# STM32.net
KiCad netlist of a schematic drawn in Altium Designer
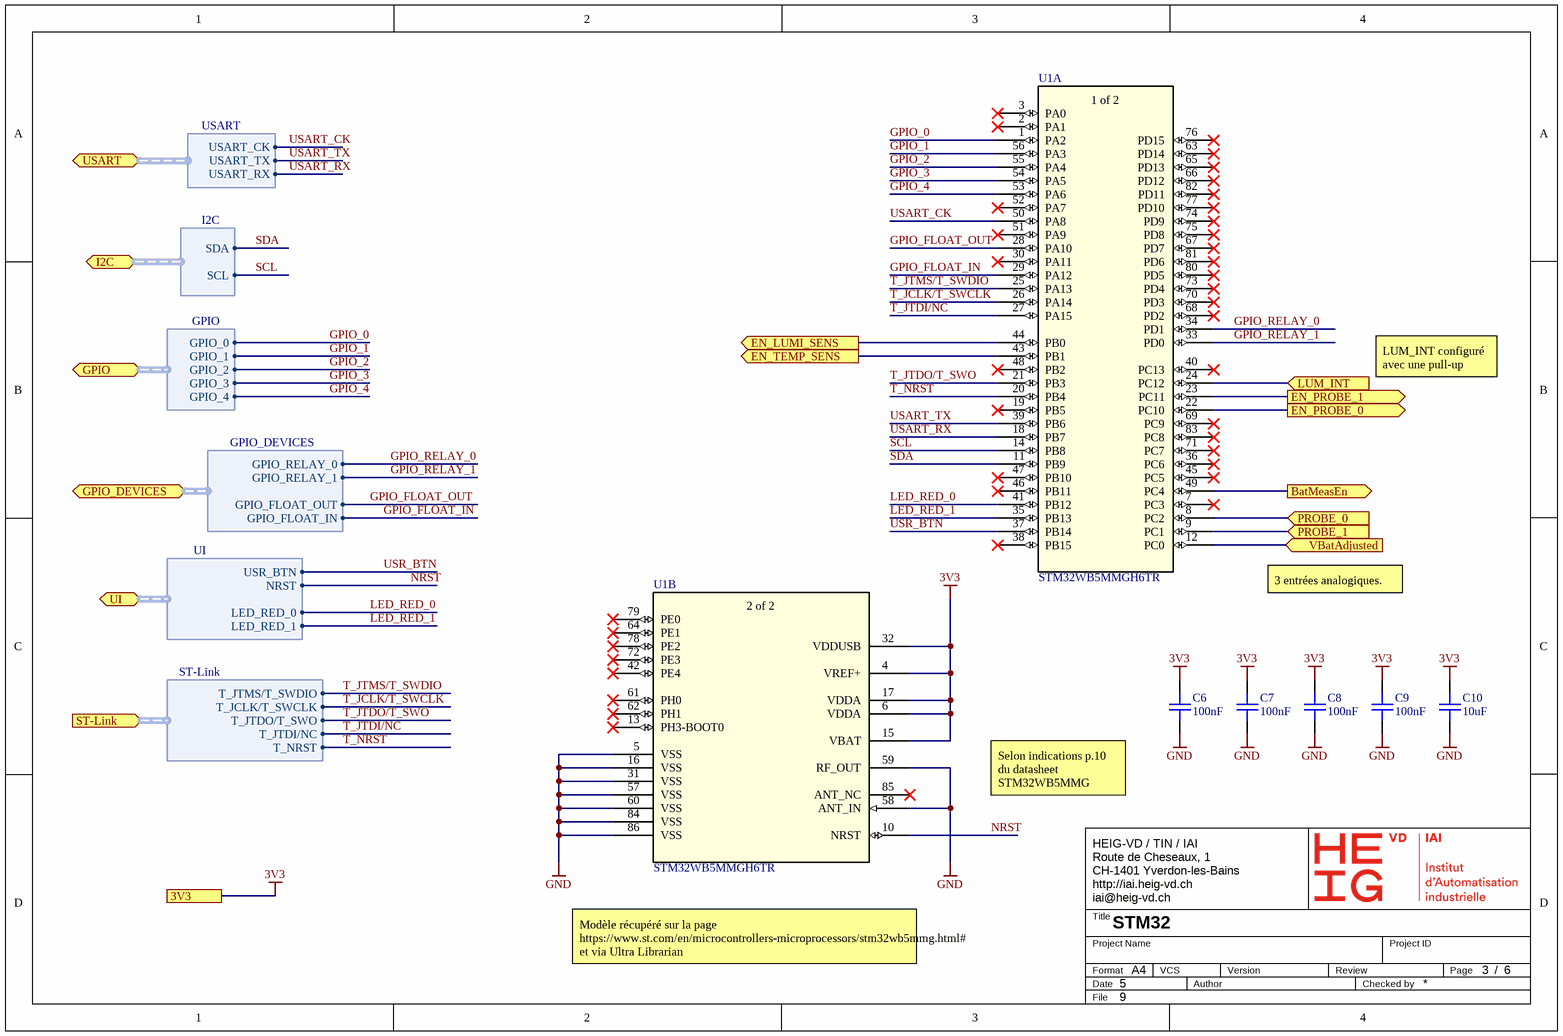
[diagram p0: STM32.SchDoc]

(export (version "E")
  (design (tool "Eeschema 10.0.6"))
  (components
    (comp (ref "C6")
      (value "100nF")
      (footprint "CAPC1005X05N")
      (description "100nF 10% 50V Ceramic Capacitor X8L 0402 (1005 Metric)")
      (fields (field (name "TOLERANCE") "10%"))
      (libsource (lib "HEIG-VD Pro") (part "Capacitor"))
    )
    (comp (ref "C7")
      (value "100nF")
      (footprint "CAPC1005X05N")
      (description "100nF 10% 50V Ceramic Capacitor X8L 0402 (1005 Metric)")
      (fields (field (name "TOLERANCE") "10%"))
      (libsource (lib "HEIG-VD Pro") (part "Capacitor"))
    )
    (comp (ref "C8")
      (value "100nF")
      (footprint "CAPC1005X05N")
      (description "100nF 10% 50V Ceramic Capacitor X8L 0402 (1005 Metric)")
      (fields (field (name "TOLERANCE") "10%"))
      (libsource (lib "HEIG-VD Pro") (part "Capacitor"))
    )
    (comp (ref "C9")
      (value "100nF")
      (footprint "CAPC1005X05N")
      (description "100nF 10% 50V Ceramic Capacitor X8L 0402 (1005 Metric)")
      (fields (field (name "TOLERANCE") "10%"))
      (libsource (lib "HEIG-VD Pro") (part "Capacitor"))
    )
    (comp (ref "C10")
      (value "10uF")
      (footprint "CAPC3216X18N")
      (description "10 µF ±10% 50V Ceramic Capacitor X7R 1206 (3216 Metric)")
      (fields (field (name "TOLERANCE") "10%"))
      (libsource (lib "HEIG-VD Pro") (part "Capacitor"))
    )
    (comp (ref "U1")
      (value "STM32WB5MMGH6TR")
      (footprint "SIP-LGA86_STM")
      (description "No Description Available")
      (libsource (lib "STM32WB5MMGH6TR") (part "STM32WB5MMGH6TR"))
    )
  )
  (nets
    (net (code "7") (name "/BatMeasEn") (class "Default")
      (node (ref "U1") (pin "49") (pinfunction "PC4_49") (pintype "bidirectional"))
    )
    (net (code "8") (name "/EN_LUMI_SENS") (class "Default")
      (node (ref "U1") (pin "44") (pinfunction "PB0_44") (pintype "bidirectional"))
    )
    (net (code "9") (name "/EN_PROBE_0") (class "Default")
      (node (ref "U1") (pin "22") (pinfunction "PC10_22") (pintype "bidirectional"))
    )
    (net (code "10") (name "/EN_PROBE_1") (class "Default")
      (node (ref "U1") (pin "23") (pinfunction "PC11_23") (pintype "bidirectional"))
    )
    (net (code "11") (name "/EN_TEMP_SENS") (class "Default")
      (node (ref "U1") (pin "43") (pinfunction "PB1_43") (pintype "bidirectional"))
    )
    (net (code "12") (name "/GPIO_0") (class "Default")
      (node (ref "U1") (pin "1") (pinfunction "PA2_1") (pintype "bidirectional"))
    )
    (net (code "13") (name "/GPIO_1") (class "Default")
      (node (ref "U1") (pin "56") (pinfunction "PA3_56") (pintype "bidirectional"))
    )
    (net (code "14") (name "/GPIO_2") (class "Default")
      (node (ref "U1") (pin "55") (pinfunction "PA4_55") (pintype "bidirectional"))
    )
    (net (code "15") (name "/GPIO_3") (class "Default")
      (node (ref "U1") (pin "54") (pinfunction "PA5_54") (pintype "bidirectional"))
    )
    (net (code "16") (name "/GPIO_4") (class "Default")
      (node (ref "U1") (pin "53") (pinfunction "PA6_53") (pintype "bidirectional"))
    )
    (net (code "17") (name "/GPIO_FLOAT_IN") (class "Default")
      (node (ref "U1") (pin "29") (pinfunction "PA12_29") (pintype "bidirectional"))
    )
    (net (code "18") (name "/GPIO_FLOAT_OUT") (class "Default")
      (node (ref "U1") (pin "28") (pinfunction "PA10_28") (pintype "bidirectional"))
    )
    (net (code "19") (name "/GPIO_RELAY_0") (class "Default")
      (node (ref "U1") (pin "34") (pinfunction "PD1_34") (pintype "bidirectional"))
    )
    (net (code "20") (name "/GPIO_RELAY_1") (class "Default")
      (node (ref "U1") (pin "33") (pinfunction "PD0_33") (pintype "bidirectional"))
    )
    (net (code "21") (name "/LED_RED_0") (class "Default")
      (node (ref "U1") (pin "41") (pinfunction "PB12_41") (pintype "bidirectional"))
    )
    (net (code "22") (name "/LED_RED_1") (class "Default")
      (node (ref "U1") (pin "35") (pinfunction "PB13_35") (pintype "bidirectional"))
    )
    (net (code "23") (name "/LUM_INT") (class "Default")
      (node (ref "U1") (pin "24") (pinfunction "PC12_24") (pintype "bidirectional"))
    )
    (net (code "24") (name "/NRST") (class "Default")
      (node (ref "U1") (pin "10") (pinfunction "NRST_10") (pintype "bidirectional"))
    )
    (net (code "25") (name "/PROBE_0") (class "Default")
      (node (ref "U1") (pin "8") (pinfunction "PC2_8") (pintype "bidirectional"))
    )
    (net (code "26") (name "/PROBE_1") (class "Default")
      (node (ref "U1") (pin "9") (pinfunction "PC1_9") (pintype "bidirectional"))
    )
    (net (code "27") (name "/SCL") (class "Default")
      (node (ref "U1") (pin "14") (pinfunction "PB8_14") (pintype "bidirectional"))
    )
    (net (code "28") (name "/SDA") (class "Default")
      (node (ref "U1") (pin "11") (pinfunction "PB9_11") (pintype "bidirectional"))
    )
    (net (code "29") (name "/T_JCLK{slash}T_SWCLK") (class "Default")
      (node (ref "U1") (pin "26") (pinfunction "PA14_26") (pintype "bidirectional"))
    )
    (net (code "30") (name "/T_JTDI{slash}NC") (class "Default")
      (node (ref "U1") (pin "27") (pinfunction "PA15_27") (pintype "bidirectional"))
    )
    (net (code "31") (name "/T_JTDO{slash}T_SWO") (class "Default")
      (node (ref "U1") (pin "21") (pinfunction "PB3_21") (pintype "bidirectional"))
    )
    (net (code "32") (name "/T_JTMS{slash}T_SWDIO") (class "Default")
      (node (ref "U1") (pin "25") (pinfunction "PA13_25") (pintype "bidirectional"))
    )
    (net (code "33") (name "/T_NRST") (class "Default")
      (node (ref "U1") (pin "20") (pinfunction "PB4_20") (pintype "bidirectional"))
    )
    (net (code "34") (name "/USART_CK") (class "Default")
      (node (ref "U1") (pin "50") (pinfunction "PA8_50") (pintype "bidirectional"))
    )
    (net (code "35") (name "/USART_RX") (class "Default")
      (node (ref "U1") (pin "18") (pinfunction "PB7_18") (pintype "bidirectional"))
    )
    (net (code "36") (name "/USART_TX") (class "Default")
      (node (ref "U1") (pin "39") (pinfunction "PB6_39") (pintype "bidirectional"))
    )
    (net (code "37") (name "/USR_BTN") (class "Default")
      (node (ref "U1") (pin "37") (pinfunction "PB14_37") (pintype "bidirectional"))
    )
    (net (code "38") (name "/VBatAdjusted") (class "Default")
      (node (ref "U1") (pin "12") (pinfunction "PC0_12") (pintype "bidirectional"))
    )
    (net (code "45") (name "3V3") (class "Default")
      (node (ref "C10") (pin "2") (pinfunction "2_2") (pintype "passive"))
      (node (ref "C6") (pin "1") (pinfunction "1_1") (pintype "passive"))
      (node (ref "C7") (pin "1") (pinfunction "1_1") (pintype "passive"))
      (node (ref "C8") (pin "1") (pinfunction "1_1") (pintype "passive"))
      (node (ref "C9") (pin "1") (pinfunction "1_1") (pintype "passive"))
      (node (ref "U1") (pin "15") (pinfunction "VBAT_15") (pintype "power_in"))
      (node (ref "U1") (pin "17") (pinfunction "VDDA_17") (pintype "power_in"))
      (node (ref "U1") (pin "32") (pinfunction "VDDUSB_32") (pintype "power_in"))
      (node (ref "U1") (pin "4") (pinfunction "VREF+_4") (pintype "power_in"))
      (node (ref "U1") (pin "6") (pinfunction "VDDA_6") (pintype "power_in"))
    )
    (net (code "46") (name "GND") (class "Default")
      (node (ref "C10") (pin "1") (pinfunction "1_1") (pintype "passive"))
      (node (ref "C6") (pin "2") (pinfunction "2_2") (pintype "passive"))
      (node (ref "C7") (pin "2") (pinfunction "2_2") (pintype "passive"))
      (node (ref "C8") (pin "2") (pinfunction "2_2") (pintype "passive"))
      (node (ref "C9") (pin "2") (pinfunction "2_2") (pintype "passive"))
      (node (ref "U1") (pin "16") (pinfunction "VSS_16") (pintype "power_in"))
      (node (ref "U1") (pin "31") (pinfunction "VSS_31") (pintype "power_in"))
      (node (ref "U1") (pin "5") (pinfunction "VSS_5") (pintype "power_in"))
      (node (ref "U1") (pin "57") (pinfunction "VSS_57") (pintype "power_in"))
      (node (ref "U1") (pin "58") (pinfunction "ANT_IN_58") (pintype "input"))
      (node (ref "U1") (pin "59") (pinfunction "RF_OUT_59") (pintype "output"))
      (node (ref "U1") (pin "60") (pinfunction "VSS_60") (pintype "power_in"))
      (node (ref "U1") (pin "84") (pinfunction "VSS_84") (pintype "power_in"))
      (node (ref "U1") (pin "86") (pinfunction "VSS_86") (pintype "power_in"))
    )
    (net (code "47") (name "unconnected-(U1A-PA0-Pad3)") (class "Default")
      (node (ref "U1") (pin "3") (pinfunction "PA0_3") (pintype "bidirectional+no_connect"))
    )
    (net (code "48") (name "unconnected-(U1A-PA1-Pad2)") (class "Default")
      (node (ref "U1") (pin "2") (pinfunction "PA1_2") (pintype "bidirectional+no_connect"))
    )
    (net (code "49") (name "unconnected-(U1A-PA7-Pad52)") (class "Default")
      (node (ref "U1") (pin "52") (pinfunction "PA7_52") (pintype "bidirectional+no_connect"))
    )
    (net (code "50") (name "unconnected-(U1A-PA9-Pad51)") (class "Default")
      (node (ref "U1") (pin "51") (pinfunction "PA9_51") (pintype "bidirectional+no_connect"))
    )
    (net (code "51") (name "unconnected-(U1A-PA11-Pad30)") (class "Default")
      (node (ref "U1") (pin "30") (pinfunction "PA11_30") (pintype "bidirectional+no_connect"))
    )
    (net (code "52") (name "unconnected-(U1A-PB2-Pad48)") (class "Default")
      (node (ref "U1") (pin "48") (pinfunction "PB2_48") (pintype "bidirectional+no_connect"))
    )
    (net (code "53") (name "unconnected-(U1A-PB5-Pad19)") (class "Default")
      (node (ref "U1") (pin "19") (pinfunction "PB5_19") (pintype "bidirectional+no_connect"))
    )
    (net (code "54") (name "unconnected-(U1A-PB10-Pad47)") (class "Default")
      (node (ref "U1") (pin "47") (pinfunction "PB10_47") (pintype "bidirectional+no_connect"))
    )
    (net (code "55") (name "unconnected-(U1A-PB11-Pad46)") (class "Default")
      (node (ref "U1") (pin "46") (pinfunction "PB11_46") (pintype "bidirectional+no_connect"))
    )
    (net (code "56") (name "unconnected-(U1A-PB15-Pad38)") (class "Default")
      (node (ref "U1") (pin "38") (pinfunction "PB15_38") (pintype "bidirectional+no_connect"))
    )
    (net (code "57") (name "unconnected-(U1A-PC3-Pad7)") (class "Default")
      (node (ref "U1") (pin "7") (pinfunction "PC3_7") (pintype "bidirectional+no_connect"))
    )
    (net (code "58") (name "unconnected-(U1A-PC5-Pad45)") (class "Default")
      (node (ref "U1") (pin "45") (pinfunction "PC5_45") (pintype "bidirectional+no_connect"))
    )
    (net (code "59") (name "unconnected-(U1A-PC6-Pad36)") (class "Default")
      (node (ref "U1") (pin "36") (pinfunction "PC6_36") (pintype "bidirectional+no_connect"))
    )
    (net (code "60") (name "unconnected-(U1A-PC7-Pad71)") (class "Default")
      (node (ref "U1") (pin "71") (pinfunction "PC7_71") (pintype "bidirectional+no_connect"))
    )
    (net (code "61") (name "unconnected-(U1A-PC8-Pad83)") (class "Default")
      (node (ref "U1") (pin "83") (pinfunction "PC8_83") (pintype "bidirectional+no_connect"))
    )
    (net (code "62") (name "unconnected-(U1A-PC9-Pad69)") (class "Default")
      (node (ref "U1") (pin "69") (pinfunction "PC9_69") (pintype "bidirectional+no_connect"))
    )
    (net (code "63") (name "unconnected-(U1A-PC13-Pad40)") (class "Default")
      (node (ref "U1") (pin "40") (pinfunction "PC13_40") (pintype "bidirectional+no_connect"))
    )
    (net (code "64") (name "unconnected-(U1A-PD2-Pad68)") (class "Default")
      (node (ref "U1") (pin "68") (pinfunction "PD2_68") (pintype "bidirectional+no_connect"))
    )
    (net (code "65") (name "unconnected-(U1A-PD3-Pad70)") (class "Default")
      (node (ref "U1") (pin "70") (pinfunction "PD3_70") (pintype "bidirectional+no_connect"))
    )
    (net (code "66") (name "unconnected-(U1A-PD4-Pad73)") (class "Default")
      (node (ref "U1") (pin "73") (pinfunction "PD4_73") (pintype "bidirectional+no_connect"))
    )
    (net (code "67") (name "unconnected-(U1A-PD5-Pad80)") (class "Default")
      (node (ref "U1") (pin "80") (pinfunction "PD5_80") (pintype "bidirectional+no_connect"))
    )
    (net (code "68") (name "unconnected-(U1A-PD6-Pad81)") (class "Default")
      (node (ref "U1") (pin "81") (pinfunction "PD6_81") (pintype "bidirectional+no_connect"))
    )
    (net (code "69") (name "unconnected-(U1A-PD7-Pad67)") (class "Default")
      (node (ref "U1") (pin "67") (pinfunction "PD7_67") (pintype "bidirectional+no_connect"))
    )
    (net (code "70") (name "unconnected-(U1A-PD8-Pad75)") (class "Default")
      (node (ref "U1") (pin "75") (pinfunction "PD8_75") (pintype "bidirectional+no_connect"))
    )
    (net (code "71") (name "unconnected-(U1A-PD9-Pad74)") (class "Default")
      (node (ref "U1") (pin "74") (pinfunction "PD9_74") (pintype "bidirectional+no_connect"))
    )
    (net (code "72") (name "unconnected-(U1A-PD10-Pad77)") (class "Default")
      (node (ref "U1") (pin "77") (pinfunction "PD10_77") (pintype "bidirectional+no_connect"))
    )
    (net (code "73") (name "unconnected-(U1A-PD11-Pad82)") (class "Default")
      (node (ref "U1") (pin "82") (pinfunction "PD11_82") (pintype "bidirectional+no_connect"))
    )
    (net (code "74") (name "unconnected-(U1A-PD12-Pad66)") (class "Default")
      (node (ref "U1") (pin "66") (pinfunction "PD12_66") (pintype "bidirectional+no_connect"))
    )
    (net (code "75") (name "unconnected-(U1A-PD13-Pad65)") (class "Default")
      (node (ref "U1") (pin "65") (pinfunction "PD13_65") (pintype "bidirectional+no_connect"))
    )
    (net (code "76") (name "unconnected-(U1A-PD14-Pad63)") (class "Default")
      (node (ref "U1") (pin "63") (pinfunction "PD14_63") (pintype "bidirectional+no_connect"))
    )
    (net (code "77") (name "unconnected-(U1A-PD15-Pad76)") (class "Default")
      (node (ref "U1") (pin "76") (pinfunction "PD15_76") (pintype "bidirectional+no_connect"))
    )
    (net (code "78") (name "unconnected-(U1B-ANT_NC-Pad85)") (class "Default")
      (node (ref "U1") (pin "85") (pinfunction "ANT_NC_85") (pintype "passive+no_connect"))
    )
    (net (code "79") (name "unconnected-(U1B-PE0-Pad79)") (class "Default")
      (node (ref "U1") (pin "79") (pinfunction "PE0_79") (pintype "bidirectional+no_connect"))
    )
    (net (code "80") (name "unconnected-(U1B-PE1-Pad64)") (class "Default")
      (node (ref "U1") (pin "64") (pinfunction "PE1_64") (pintype "bidirectional+no_connect"))
    )
    (net (code "81") (name "unconnected-(U1B-PE2-Pad78)") (class "Default")
      (node (ref "U1") (pin "78") (pinfunction "PE2_78") (pintype "bidirectional+no_connect"))
    )
    (net (code "82") (name "unconnected-(U1B-PE3-Pad72)") (class "Default")
      (node (ref "U1") (pin "72") (pinfunction "PE3_72") (pintype "bidirectional+no_connect"))
    )
    (net (code "83") (name "unconnected-(U1B-PE4-Pad42)") (class "Default")
      (node (ref "U1") (pin "42") (pinfunction "PE4_42") (pintype "bidirectional+no_connect"))
    )
    (net (code "84") (name "unconnected-(U1B-PH0-Pad61)") (class "Default")
      (node (ref "U1") (pin "61") (pinfunction "PH0_61") (pintype "bidirectional+no_connect"))
    )
    (net (code "85") (name "unconnected-(U1B-PH1-Pad62)") (class "Default")
      (node (ref "U1") (pin "62") (pinfunction "PH1_62") (pintype "bidirectional+no_connect"))
    )
    (net (code "86") (name "unconnected-(U1B-PH3-BOOT0-Pad13)") (class "Default")
      (node (ref "U1") (pin "13") (pinfunction "PH3-BOOT0_13") (pintype "bidirectional+no_connect"))
    )
  )
)
